# micro.net
KiCad netlist of a schematic drawn in EAGLE
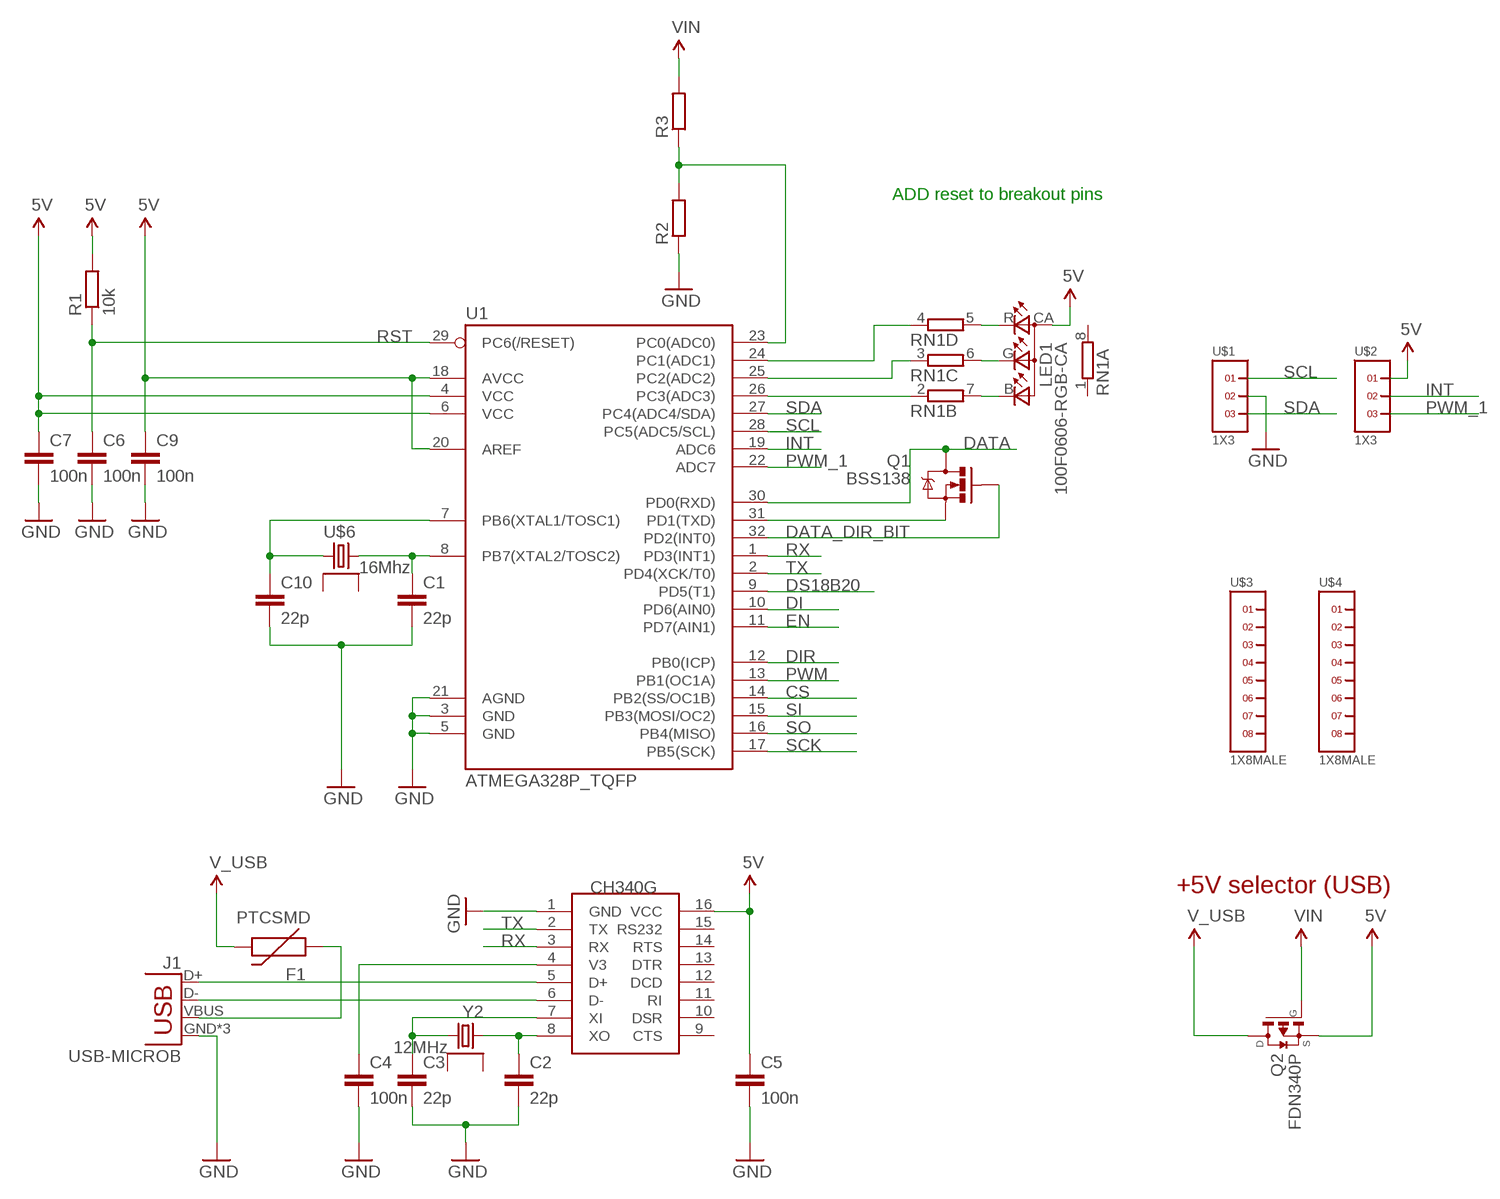
[diagram p0: schematic, sheet 1]

(export (version "E")
  (design (tool "Eeschema 10.0.6"))
  (components
    (comp (ref "C1")
      (value "22p")
      (footprint "eagle-import:C0402K")
      (libsource (lib "eagle-import") (part "C-EUC0402K"))
    )
    (comp (ref "C2")
      (value "22p")
      (footprint "eagle-import:C0402K")
      (libsource (lib "eagle-import") (part "C-EUC0402K"))
    )
    (comp (ref "C3")
      (value "22p")
      (footprint "eagle-import:C0402K")
      (libsource (lib "eagle-import") (part "C-EUC0402K"))
    )
    (comp (ref "C4")
      (value "100n")
      (footprint "eagle-import:C0402K")
      (libsource (lib "eagle-import") (part "C-EUC0402K"))
    )
    (comp (ref "C5")
      (value "100n")
      (footprint "eagle-import:C0402K")
      (libsource (lib "eagle-import") (part "C-EUC0402K"))
    )
    (comp (ref "C6")
      (value "100n")
      (footprint "eagle-import:C0402K")
      (libsource (lib "eagle-import") (part "C-EUC0402K"))
    )
    (comp (ref "C7")
      (value "100n")
      (footprint "eagle-import:C0402K")
      (libsource (lib "eagle-import") (part "C-EUC0402K"))
    )
    (comp (ref "C9")
      (value "100n")
      (footprint "eagle-import:C0402K")
      (libsource (lib "eagle-import") (part "C-EUC0402K"))
    )
    (comp (ref "C10")
      (value "22p")
      (footprint "eagle-import:C0402K")
      (libsource (lib "eagle-import") (part "C-EUC0402K"))
    )
    (comp (ref "F1")
      (value "PTCSMD")
      (footprint "eagle-import:PTC-1206")
      (libsource (lib "eagle-import") (part "PTCSMD"))
    )
    (comp (ref "J1")
      (value "USB-MICROB")
      (footprint "eagle-import:USB-MICROB")
      (libsource (lib "eagle-import") (part "USB-MICROB"))
    )
    (comp (ref "LED1")
      (value "100F0606-RGB-CA")
      (footprint "eagle-import:1616")
      (libsource (lib "eagle-import") (part "100F0606-RGB-CA"))
    )
    (comp (ref "Q1")
      (value "BSS138")
      (footprint "eagle-import:SOT23-3")
      (libsource (lib "eagle-import") (part "MOSFET-NCHANNELBSS138"))
    )
    (comp (ref "Q2")
      (value "FDN340P")
      (footprint "eagle-import:SSOT-3")
      (libsource (lib "eagle-import") (part "FDN340P"))
    )
    (comp (ref "R1")
      (value "10k")
      (footprint "eagle-import:R0402")
      (libsource (lib "eagle-import") (part "R-EU_R0402"))
    )
    (comp (ref "R2")
      (value "R-EU_R0402")
      (footprint "eagle-import:R0402")
      (libsource (lib "eagle-import") (part "R-EU_R0402"))
    )
    (comp (ref "R3")
      (value "R-EU_R0402")
      (footprint "eagle-import:R0402")
      (libsource (lib "eagle-import") (part "R-EU_R0402"))
    )
    (comp (ref "RN1")
      (value "4R-NYC124")
      (footprint "eagle-import:YC124")
      (libsource (lib "eagle-import") (part "4R-NYC124"))
    )
    (comp (ref "U$1")
      (value "1X3")
      (footprint "eagle-import:1X3")
      (libsource (lib "eagle-import") (part "1X3"))
    )
    (comp (ref "U$2")
      (value "1X3")
      (footprint "eagle-import:1X3")
      (libsource (lib "eagle-import") (part "1X3"))
    )
    (comp (ref "U$3")
      (value "1X8MALE")
      (footprint "eagle-import:1X8_MALE")
      (libsource (lib "eagle-import") (part "1X8MALE"))
    )
    (comp (ref "U$4")
      (value "1X8MALE")
      (footprint "eagle-import:1X8_MALE")
      (libsource (lib "eagle-import") (part "1X8MALE"))
    )
    (comp (ref "U$5")
      (value "CH340G")
      (footprint "eagle-import:SOIC16")
      (libsource (lib "eagle-import") (part "CH340G"))
    )
    (comp (ref "U$6")
      (value "16Mhz")
      (footprint "eagle-import:OSC3225")
      (libsource (lib "eagle-import") (part "GSX-331"))
    )
    (comp (ref "U1")
      (value "ATMEGA328P_TQFP")
      (footprint "eagle-import:TQFP32-08")
      (libsource (lib "eagle-import") (part "ATMEGA328P_TQFP"))
    )
    (comp (ref "Y2")
      (value "12MHz")
      (footprint "eagle-import:GSX-531")
      (libsource (lib "eagle-import") (part "GSX-531"))
    )
  )
  (nets
    (net (code "1") (name "/CS") (class "Default")
      (node (ref "U1") (pin "14") (pinfunction "PB2(SS/OC1B)_14") (pintype "bidirectional"))
    )
    (net (code "2") (name "/DATA") (class "Default")
      (node (ref "Q1") (pin "3") (pinfunction "D_3") (pintype "passive"))
      (node (ref "U1") (pin "30") (pinfunction "PD0(RXD)_30") (pintype "bidirectional"))
    )
    (net (code "3") (name "/DATA_DIR_BIT") (class "Default")
      (node (ref "Q1") (pin "1") (pinfunction "G_1") (pintype "passive"))
      (node (ref "U1") (pin "32") (pinfunction "PD2(INT0)_32") (pintype "bidirectional"))
    )
    (net (code "4") (name "/DI") (class "Default")
      (node (ref "U1") (pin "10") (pinfunction "PD6(AIN0)_10") (pintype "bidirectional"))
    )
    (net (code "5") (name "/DIR") (class "Default")
      (node (ref "U1") (pin "12") (pinfunction "PB0(ICP)_12") (pintype "bidirectional"))
    )
    (net (code "6") (name "/DS18B20") (class "Default")
      (node (ref "U1") (pin "9") (pinfunction "PD5(T1)_9") (pintype "bidirectional"))
    )
    (net (code "7") (name "/EN") (class "Default")
      (node (ref "U1") (pin "11") (pinfunction "PD7(AIN1)_11") (pintype "bidirectional"))
    )
    (net (code "8") (name "/INT") (class "Default")
      (node (ref "U$2") (pin "2") (pinfunction "2_2") (pintype "bidirectional"))
      (node (ref "U1") (pin "19") (pinfunction "ADC6_19") (pintype "bidirectional"))
    )
    (net (code "9") (name "/PWM") (class "Default")
      (node (ref "U1") (pin "13") (pinfunction "PB1(OC1A)_13") (pintype "bidirectional"))
    )
    (net (code "10") (name "/PWM_1") (class "Default")
      (node (ref "U$2") (pin "3") (pinfunction "3_3") (pintype "bidirectional"))
      (node (ref "U1") (pin "22") (pinfunction "ADC7_22") (pintype "bidirectional"))
    )
    (net (code "11") (name "/RST") (class "Default")
      (node (ref "C6") (pin "1") (pinfunction "1_1") (pintype "passive"))
      (node (ref "R1") (pin "1") (pinfunction "1_1") (pintype "passive"))
      (node (ref "U1") (pin "29") (pinfunction "PC6(/RESET)_29") (pintype "bidirectional"))
    )
    (net (code "12") (name "/RX") (class "Default")
      (node (ref "U$5") (pin "3") (pinfunction "RX_3") (pintype "bidirectional"))
      (node (ref "U1") (pin "1") (pinfunction "PD3(INT1)_1") (pintype "bidirectional"))
    )
    (net (code "13") (name "/SCK") (class "Default")
      (node (ref "U1") (pin "17") (pinfunction "PB5(SCK)_17") (pintype "bidirectional"))
    )
    (net (code "14") (name "/SCL") (class "Default")
      (node (ref "U$1") (pin "1") (pinfunction "1_1") (pintype "bidirectional"))
      (node (ref "U1") (pin "28") (pinfunction "PC5(ADC5/SCL)_28") (pintype "bidirectional"))
    )
    (net (code "15") (name "/SDA") (class "Default")
      (node (ref "U$1") (pin "3") (pinfunction "3_3") (pintype "bidirectional"))
      (node (ref "U1") (pin "27") (pinfunction "PC4(ADC4/SDA)_27") (pintype "bidirectional"))
    )
    (net (code "16") (name "/SI") (class "Default")
      (node (ref "U1") (pin "15") (pinfunction "PB3(MOSI/OC2)_15") (pintype "bidirectional"))
    )
    (net (code "17") (name "/SO") (class "Default")
      (node (ref "U1") (pin "16") (pinfunction "PB4(MISO)_16") (pintype "bidirectional"))
    )
    (net (code "18") (name "/TX") (class "Default")
      (node (ref "U$5") (pin "2") (pinfunction "TX_2") (pintype "bidirectional"))
      (node (ref "U1") (pin "2") (pinfunction "PD4(XCK/T0)_2") (pintype "bidirectional"))
    )
    (net (code "19") (name "5V") (class "Default")
      (node (ref "C5") (pin "1") (pinfunction "1_1") (pintype "passive"))
      (node (ref "C7") (pin "1") (pinfunction "1_1") (pintype "passive"))
      (node (ref "C9") (pin "1") (pinfunction "1_1") (pintype "passive"))
      (node (ref "LED1") (pin "CA") (pinfunction "CA_CA") (pintype "passive"))
      (node (ref "Q2") (pin "2") (pinfunction "S_2") (pintype "passive"))
      (node (ref "R1") (pin "2") (pinfunction "2_2") (pintype "passive"))
      (node (ref "U$2") (pin "1") (pinfunction "1_1") (pintype "bidirectional"))
      (node (ref "U$5") (pin "16") (pinfunction "VCC_16") (pintype "bidirectional"))
      (node (ref "U1") (pin "18") (pinfunction "AVCC_18") (pintype "bidirectional"))
      (node (ref "U1") (pin "20") (pinfunction "AREF_20") (pintype "bidirectional"))
      (node (ref "U1") (pin "4") (pinfunction "VCC_4") (pintype "bidirectional"))
      (node (ref "U1") (pin "6") (pinfunction "VCC_6") (pintype "bidirectional"))
    )
    (net (code "20") (name "GND") (class "Default")
      (node (ref "C1") (pin "2") (pinfunction "2_2") (pintype "passive"))
      (node (ref "C10") (pin "2") (pinfunction "2_2") (pintype "passive"))
      (node (ref "C2") (pin "2") (pinfunction "2_2") (pintype "passive"))
      (node (ref "C3") (pin "2") (pinfunction "2_2") (pintype "passive"))
      (node (ref "C4") (pin "2") (pinfunction "2_2") (pintype "passive"))
      (node (ref "C5") (pin "2") (pinfunction "2_2") (pintype "passive"))
      (node (ref "C6") (pin "2") (pinfunction "2_2") (pintype "passive"))
      (node (ref "C7") (pin "2") (pinfunction "2_2") (pintype "passive"))
      (node (ref "C9") (pin "2") (pinfunction "2_2") (pintype "passive"))
      (node (ref "J1") (pin "GND") (pinfunction "GND_GND") (pintype "bidirectional"))
      (node (ref "J1") (pin "MT1") (pinfunction "GND_MT1") (pintype "bidirectional"))
      (node (ref "J1") (pin "MT2") (pinfunction "GND_MT2") (pintype "bidirectional"))
      (node (ref "R2") (pin "1") (pinfunction "1_1") (pintype "passive"))
      (node (ref "U$1") (pin "2") (pinfunction "2_2") (pintype "bidirectional"))
      (node (ref "U$5") (pin "1") (pinfunction "GND_1") (pintype "bidirectional"))
      (node (ref "U1") (pin "21") (pinfunction "AGND_21") (pintype "bidirectional"))
      (node (ref "U1") (pin "3") (pinfunction "GND_3") (pintype "bidirectional"))
      (node (ref "U1") (pin "5") (pinfunction "GND_5") (pintype "bidirectional"))
    )
    (net (code "21") (name "Net-(F1-Pad1)") (class "Default")
      (node (ref "F1") (pin "1") (pinfunction "1_1") (pintype "bidirectional"))
      (node (ref "J1") (pin "VBUS") (pinfunction "VBUS_VBUS") (pintype "bidirectional"))
    )
    (net (code "22") (name "Net-(Q1-S)") (class "Default")
      (node (ref "Q1") (pin "2") (pinfunction "S_2") (pintype "passive"))
      (node (ref "U1") (pin "31") (pinfunction "PD1(TXD)_31") (pintype "bidirectional"))
    )
    (net (code "23") (name "Net-(RN1B-1)") (class "Default")
      (node (ref "RN1") (pin "2") (pinfunction "1_2") (pintype "passive"))
      (node (ref "U1") (pin "26") (pinfunction "PC3(ADC3)_26") (pintype "bidirectional"))
    )
    (net (code "24") (name "Net-(RN1B-2)") (class "Default")
      (node (ref "LED1") (pin "B") (pinfunction "B_B") (pintype "passive"))
      (node (ref "RN1") (pin "7") (pinfunction "2_7") (pintype "passive"))
    )
    (net (code "25") (name "Net-(RN1C-1)") (class "Default")
      (node (ref "RN1") (pin "3") (pinfunction "1_3") (pintype "passive"))
      (node (ref "U1") (pin "25") (pinfunction "PC2(ADC2)_25") (pintype "bidirectional"))
    )
    (net (code "26") (name "Net-(RN1C-2)") (class "Default")
      (node (ref "LED1") (pin "G") (pinfunction "G_G") (pintype "passive"))
      (node (ref "RN1") (pin "6") (pinfunction "2_6") (pintype "passive"))
    )
    (net (code "27") (name "Net-(RN1D-1)") (class "Default")
      (node (ref "RN1") (pin "4") (pinfunction "1_4") (pintype "passive"))
      (node (ref "U1") (pin "24") (pinfunction "PC1(ADC1)_24") (pintype "bidirectional"))
    )
    (net (code "28") (name "Net-(RN1D-2)") (class "Default")
      (node (ref "LED1") (pin "R") (pinfunction "R_R") (pintype "passive"))
      (node (ref "RN1") (pin "5") (pinfunction "2_5") (pintype "passive"))
    )
    (net (code "29") (name "Net-(U$5-D+)") (class "Default")
      (node (ref "J1") (pin "D+") (pinfunction "D+_D+") (pintype "bidirectional"))
      (node (ref "U$5") (pin "5") (pinfunction "D+_5") (pintype "bidirectional"))
    )
    (net (code "30") (name "Net-(U$5-D-)") (class "Default")
      (node (ref "J1") (pin "D-") (pinfunction "D-_D-") (pintype "bidirectional"))
      (node (ref "U$5") (pin "6") (pinfunction "D-_6") (pintype "bidirectional"))
    )
    (net (code "31") (name "Net-(U$5-V3)") (class "Default")
      (node (ref "C4") (pin "1") (pinfunction "1_1") (pintype "passive"))
      (node (ref "U$5") (pin "4") (pinfunction "V3_4") (pintype "bidirectional"))
    )
    (net (code "32") (name "Net-(U$5-XI)") (class "Default")
      (node (ref "C3") (pin "1") (pinfunction "1_1") (pintype "passive"))
      (node (ref "U$5") (pin "7") (pinfunction "XI_7") (pintype "bidirectional"))
      (node (ref "Y2") (pin "P$3") (pinfunction "3_P$3") (pintype "passive"))
    )
    (net (code "33") (name "Net-(U$5-XO)") (class "Default")
      (node (ref "C2") (pin "1") (pinfunction "1_1") (pintype "passive"))
      (node (ref "U$5") (pin "8") (pinfunction "XO_8") (pintype "bidirectional"))
      (node (ref "Y2") (pin "P$1") (pinfunction "1_P$1") (pintype "passive"))
    )
    (net (code "34") (name "Net-(U$6-1)") (class "Default")
      (node (ref "C10") (pin "1") (pinfunction "1_1") (pintype "passive"))
      (node (ref "U$6") (pin "P$1") (pinfunction "1_P$1") (pintype "passive"))
      (node (ref "U1") (pin "7") (pinfunction "PB6(XTAL1/TOSC1)_7") (pintype "bidirectional"))
    )
    (net (code "35") (name "Net-(U$6-3)") (class "Default")
      (node (ref "C1") (pin "1") (pinfunction "1_1") (pintype "passive"))
      (node (ref "U$6") (pin "P$3") (pinfunction "3_P$3") (pintype "passive"))
      (node (ref "U1") (pin "8") (pinfunction "PB7(XTAL2/TOSC2)_8") (pintype "bidirectional"))
    )
    (net (code "36") (name "Net-(U1-PC0(ADC0))") (class "Default")
      (node (ref "R2") (pin "2") (pinfunction "2_2") (pintype "passive"))
      (node (ref "R3") (pin "1") (pinfunction "1_1") (pintype "passive"))
      (node (ref "U1") (pin "23") (pinfunction "PC0(ADC0)_23") (pintype "bidirectional"))
    )
    (net (code "37") (name "VIN") (class "Default")
      (node (ref "Q2") (pin "1") (pinfunction "G_1") (pintype "passive"))
      (node (ref "R3") (pin "2") (pinfunction "2_2") (pintype "passive"))
    )
    (net (code "38") (name "V_USB") (class "Default")
      (node (ref "F1") (pin "2") (pinfunction "2_2") (pintype "bidirectional"))
      (node (ref "Q2") (pin "3") (pinfunction "D_3") (pintype "passive"))
    )
    (net (code "39") (name "unconnected-(RN1-Pad1)") (class "Default")
      (node (ref "RN1") (pin "1") (pinfunction "1_1") (pintype "passive"))
    )
    (net (code "40") (name "unconnected-(RN1A-2-Pad8)") (class "Default")
      (node (ref "RN1") (pin "8") (pinfunction "2_8") (pintype "passive"))
    )
    (net (code "41") (name "unconnected-(U$3-Pad1)") (class "Default")
      (node (ref "U$3") (pin "1") (pinfunction "1_1") (pintype "bidirectional"))
    )
    (net (code "42") (name "unconnected-(U$3-Pad2)") (class "Default")
      (node (ref "U$3") (pin "2") (pinfunction "2_2") (pintype "bidirectional"))
    )
    (net (code "43") (name "unconnected-(U$3-Pad3)") (class "Default")
      (node (ref "U$3") (pin "3") (pinfunction "3_3") (pintype "bidirectional"))
    )
    (net (code "44") (name "unconnected-(U$3-Pad4)") (class "Default")
      (node (ref "U$3") (pin "4") (pinfunction "4_4") (pintype "bidirectional"))
    )
    (net (code "45") (name "unconnected-(U$3-Pad5)") (class "Default")
      (node (ref "U$3") (pin "5") (pinfunction "5_5") (pintype "bidirectional"))
    )
    (net (code "46") (name "unconnected-(U$3-Pad6)") (class "Default")
      (node (ref "U$3") (pin "6") (pinfunction "6_6") (pintype "bidirectional"))
    )
    (net (code "47") (name "unconnected-(U$3-Pad7)") (class "Default")
      (node (ref "U$3") (pin "7") (pinfunction "7_7") (pintype "bidirectional"))
    )
    (net (code "48") (name "unconnected-(U$3-Pad8)") (class "Default")
      (node (ref "U$3") (pin "8") (pinfunction "8_8") (pintype "bidirectional"))
    )
    (net (code "49") (name "unconnected-(U$4-Pad1)") (class "Default")
      (node (ref "U$4") (pin "1") (pinfunction "1_1") (pintype "bidirectional"))
    )
    (net (code "50") (name "unconnected-(U$4-Pad2)") (class "Default")
      (node (ref "U$4") (pin "2") (pinfunction "2_2") (pintype "bidirectional"))
    )
    (net (code "51") (name "unconnected-(U$4-Pad3)") (class "Default")
      (node (ref "U$4") (pin "3") (pinfunction "3_3") (pintype "bidirectional"))
    )
    (net (code "52") (name "unconnected-(U$4-Pad4)") (class "Default")
      (node (ref "U$4") (pin "4") (pinfunction "4_4") (pintype "bidirectional"))
    )
    (net (code "53") (name "unconnected-(U$4-Pad5)") (class "Default")
      (node (ref "U$4") (pin "5") (pinfunction "5_5") (pintype "bidirectional"))
    )
    (net (code "54") (name "unconnected-(U$4-Pad6)") (class "Default")
      (node (ref "U$4") (pin "6") (pinfunction "6_6") (pintype "bidirectional"))
    )
    (net (code "55") (name "unconnected-(U$4-Pad7)") (class "Default")
      (node (ref "U$4") (pin "7") (pinfunction "7_7") (pintype "bidirectional"))
    )
    (net (code "56") (name "unconnected-(U$4-Pad8)") (class "Default")
      (node (ref "U$4") (pin "8") (pinfunction "8_8") (pintype "bidirectional"))
    )
    (net (code "57") (name "unconnected-(U$5-CTS-Pad9)") (class "Default")
      (node (ref "U$5") (pin "9") (pinfunction "CTS_9") (pintype "bidirectional"))
    )
    (net (code "58") (name "unconnected-(U$5-DCD-Pad12)") (class "Default")
      (node (ref "U$5") (pin "12") (pinfunction "DCD_12") (pintype "bidirectional"))
    )
    (net (code "59") (name "unconnected-(U$5-DSR-Pad10)") (class "Default")
      (node (ref "U$5") (pin "10") (pinfunction "DSR_10") (pintype "bidirectional"))
    )
    (net (code "60") (name "unconnected-(U$5-DTR-Pad13)") (class "Default")
      (node (ref "U$5") (pin "13") (pinfunction "DTR_13") (pintype "bidirectional"))
    )
    (net (code "61") (name "unconnected-(U$5-RI-Pad11)") (class "Default")
      (node (ref "U$5") (pin "11") (pinfunction "RI_11") (pintype "bidirectional"))
    )
    (net (code "62") (name "unconnected-(U$5-RS232-Pad15)") (class "Default")
      (node (ref "U$5") (pin "15") (pinfunction "RS232_15") (pintype "bidirectional"))
    )
    (net (code "63") (name "unconnected-(U$5-RTS-Pad14)") (class "Default")
      (node (ref "U$5") (pin "14") (pinfunction "RTS_14") (pintype "bidirectional"))
    )
    (net (code "64") (name "unconnected-(U$6-2-PadP$2)") (class "Default")
      (node (ref "U$6") (pin "P$2") (pinfunction "2_P$2") (pintype "passive"))
    )
    (net (code "65") (name "unconnected-(U$6-4-PadP$4)") (class "Default")
      (node (ref "U$6") (pin "P$4") (pinfunction "4_P$4") (pintype "passive"))
    )
    (net (code "66") (name "unconnected-(Y2-2-PadP$2)") (class "Default")
      (node (ref "Y2") (pin "P$2") (pinfunction "2_P$2") (pintype "passive"))
    )
    (net (code "67") (name "unconnected-(Y2-4-PadP$4)") (class "Default")
      (node (ref "Y2") (pin "P$4") (pinfunction "4_P$4") (pintype "passive"))
    )
  )
)
